# CABLE_MKIV.net
KiCad netlist of a schematic drawn in Altium Designer
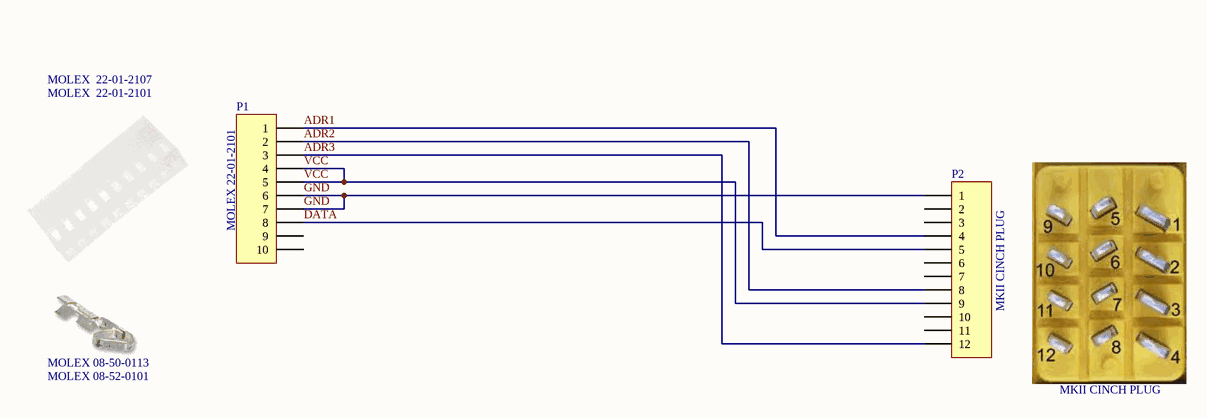
[diagram p0: CABLE MKIV.SchDoc]

(export (version "E")
  (design (tool "Eeschema 10.0.6"))
  (components
    (comp (ref "P1")
      (value "MOLEX 22-01-2101")
      (footprint "HDR1X10")
      (description "Header, 10-Pin")
      (fields (field (name "PUBLISHER") "Altium Limited"))
      (libsource (lib "Miscellaneous Connectors") (part "Header 10"))
    )
    (comp (ref "P2")
      (value "MKII CINCH PLUG")
      (footprint "HDR1X12")
      (description "Header, 12-Pin")
      (fields (field (name "PUBLISHER") "Altium Limited"))
      (libsource (lib "Miscellaneous Connectors") (part "Header 12"))
    )
  )
  (nets
    (net (code "1") (name "/ADR1") (class "Default")
      (node (ref "P1") (pin "1") (pinfunction "1_1") (pintype "passive"))
      (node (ref "P2") (pin "4") (pinfunction "4_4") (pintype "passive"))
    )
    (net (code "2") (name "/ADR2") (class "Default")
      (node (ref "P1") (pin "2") (pinfunction "2_2") (pintype "passive"))
      (node (ref "P2") (pin "8") (pinfunction "8_8") (pintype "passive"))
    )
    (net (code "3") (name "/ADR3") (class "Default")
      (node (ref "P1") (pin "3") (pinfunction "3_3") (pintype "passive"))
      (node (ref "P2") (pin "12") (pinfunction "12_12") (pintype "passive"))
    )
    (net (code "4") (name "/DATA") (class "Default")
      (node (ref "P1") (pin "8") (pinfunction "8_8") (pintype "passive"))
      (node (ref "P2") (pin "5") (pinfunction "5_5") (pintype "passive"))
    )
    (net (code "5") (name "/GND") (class "Default")
      (node (ref "P1") (pin "6") (pinfunction "6_6") (pintype "passive"))
      (node (ref "P1") (pin "7") (pinfunction "7_7") (pintype "passive"))
      (node (ref "P2") (pin "1") (pinfunction "1_1") (pintype "passive"))
    )
    (net (code "6") (name "/VCC") (class "Default")
      (node (ref "P1") (pin "4") (pinfunction "4_4") (pintype "passive"))
      (node (ref "P1") (pin "5") (pinfunction "5_5") (pintype "passive"))
      (node (ref "P2") (pin "9") (pinfunction "9_9") (pintype "passive"))
    )
    (net (code "7") (name "unconnected-(P1-Pad9)") (class "Default")
      (node (ref "P1") (pin "9") (pinfunction "9_9") (pintype "passive"))
    )
    (net (code "8") (name "unconnected-(P1-Pad10)") (class "Default")
      (node (ref "P1") (pin "10") (pinfunction "10_10") (pintype "passive"))
    )
    (net (code "9") (name "unconnected-(P2-Pad2)") (class "Default")
      (node (ref "P2") (pin "2") (pinfunction "2_2") (pintype "passive"))
    )
    (net (code "10") (name "unconnected-(P2-Pad3)") (class "Default")
      (node (ref "P2") (pin "3") (pinfunction "3_3") (pintype "passive"))
    )
    (net (code "11") (name "unconnected-(P2-Pad6)") (class "Default")
      (node (ref "P2") (pin "6") (pinfunction "6_6") (pintype "passive"))
    )
    (net (code "12") (name "unconnected-(P2-Pad7)") (class "Default")
      (node (ref "P2") (pin "7") (pinfunction "7_7") (pintype "passive"))
    )
    (net (code "13") (name "unconnected-(P2-Pad10)") (class "Default")
      (node (ref "P2") (pin "10") (pinfunction "10_10") (pintype "passive"))
    )
    (net (code "14") (name "unconnected-(P2-Pad11)") (class "Default")
      (node (ref "P2") (pin "11") (pinfunction "11_11") (pintype "passive"))
    )
  )
)
